# Option_EMCC_Flash.net
KiCad netlist of a schematic drawn in Altium Designer
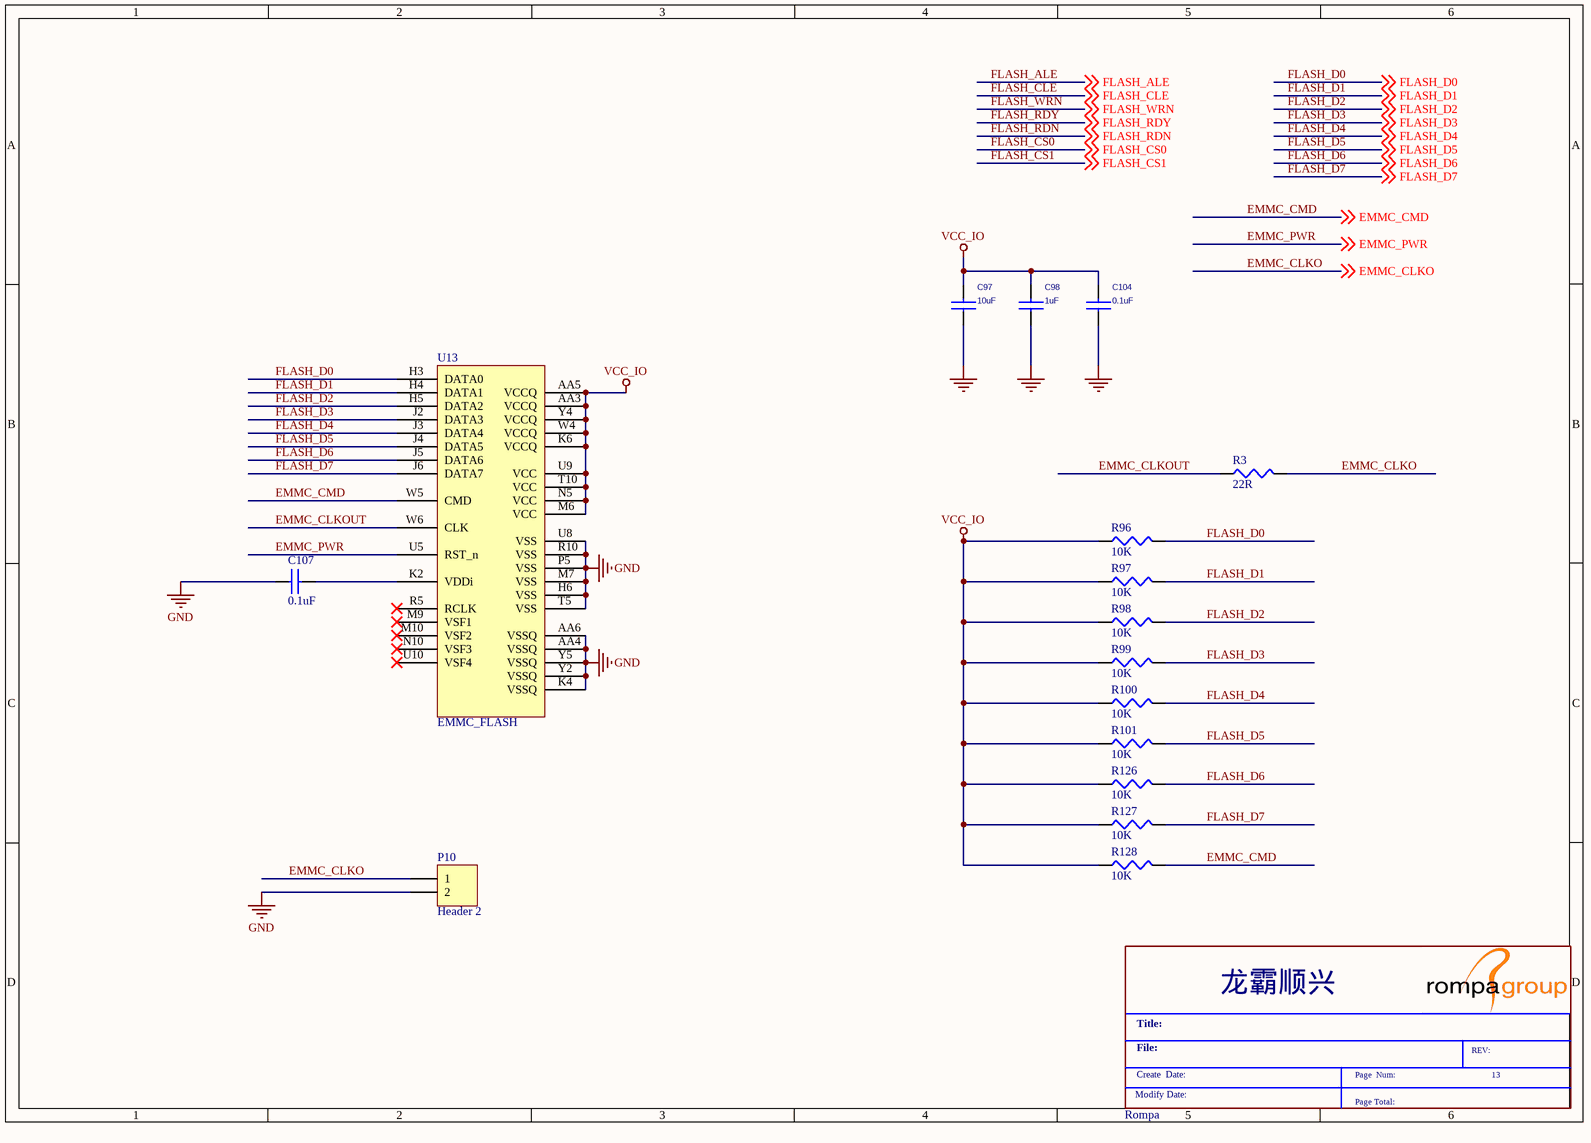
[diagram p0: Option_EMCC_Flash.SchDoc]

(export (version "E")
  (design (tool "Eeschema 10.0.6"))
  (components
    (comp (ref "*")
      (value "Rompa")
      (fields (field (name "SCHEMATIC PAGE NUMBER") "13"))
      (libsource (lib "RK3128_BETA_V03_20151231_Library") (part "Rompa"))
    )
    (comp (ref "C97") (value "10uF") (description "X5R 10%  6.3V") (libsource (lib "*") (part "CAP NP")))
    (comp (ref "C98") (value "1uF") (description "+10/-10% X5R  6.3V") (libsource (lib "*") (part "CAP NP")))
    (comp (ref "C104")
      (value "0.1uF")
      (footprint "C0402")
      (description "RoHS CHIP CAP 0.1uF +10/-10% X7R")
      (libsource (lib "*") (part "CAP NP"))
    )
    (comp (ref "C107")
      (value "0.1uF")
      (footprint "C0402")
      (libsource (lib "RK3128_BETA_V03_20151231_Library") (part "CAP NP"))
    )
    (comp (ref "P10")
      (value "Header 2")
      (footprint "HDR1X2")
      (description "Header, 2-Pin")
      (fields (field (name "PUBLISHER") "Altium Limited"))
      (libsource (lib "Miscellaneous Connectors") (part "Header 2"))
    )
    (comp (ref "R3")
      (value "22R")
      (footprint "R0402")
      (libsource (lib "RK3128_BETA_V03_20151231_Library") (part "RESISTOR"))
    )
    (comp (ref "R96")
      (value "10K")
      (footprint "R0402")
      (libsource (lib "RK3128_BETA_V03_20151231_Library") (part "RESISTOR"))
    )
    (comp (ref "R97")
      (value "10K")
      (footprint "R0402")
      (libsource (lib "RK3128_BETA_V03_20151231_Library") (part "RESISTOR"))
    )
    (comp (ref "R98")
      (value "10K")
      (footprint "R0402")
      (libsource (lib "RK3128_BETA_V03_20151231_Library") (part "RESISTOR"))
    )
    (comp (ref "R99")
      (value "10K")
      (footprint "R0402")
      (libsource (lib "RK3128_BETA_V03_20151231_Library") (part "RESISTOR"))
    )
    (comp (ref "R100")
      (value "10K")
      (footprint "R0402")
      (libsource (lib "RK3128_BETA_V03_20151231_Library") (part "RESISTOR"))
    )
    (comp (ref "R101")
      (value "10K")
      (footprint "R0402")
      (libsource (lib "RK3128_BETA_V03_20151231_Library") (part "RESISTOR"))
    )
    (comp (ref "R126")
      (value "10K")
      (footprint "R0402")
      (libsource (lib "RK3128_BETA_V03_20151231_Library") (part "RESISTOR"))
    )
    (comp (ref "R127")
      (value "10K")
      (footprint "R0402")
      (libsource (lib "RK3128_BETA_V03_20151231_Library") (part "RESISTOR"))
    )
    (comp (ref "R128")
      (value "10K")
      (footprint "R0402")
      (libsource (lib "RK3128_BETA_V03_20151231_Library") (part "RESISTOR"))
    )
    (comp (ref "U13")
      (value "EMMC_FLASH")
      (description "EMMC Flash")
      (libsource (lib "*") (part "EMMC_FLASH"))
    )
  )
  (nets
    (net (code "1") (name "/EMMC_CLKOUT") (class "Default")
      (node (ref "R3") (pin "1") (pinfunction "1_1") (pintype "passive"))
      (node (ref "U13") (pin "W6") (pinfunction "CLK_W6") (pintype "passive"))
    )
    (net (code "2") (name "EMMC_CLKO") (class "Default")
      (node (ref "P10") (pin "1") (pinfunction "1_1") (pintype "passive"))
      (node (ref "R3") (pin "2") (pinfunction "2_2") (pintype "passive"))
    )
    (net (code "3") (name "EMMC_CMD") (class "Default")
      (node (ref "R128") (pin "2") (pinfunction "2_2") (pintype "passive"))
      (node (ref "U13") (pin "W5") (pinfunction "CMD_W5") (pintype "passive"))
    )
    (net (code "4") (name "EMMC_PWR") (class "Default")
      (node (ref "U13") (pin "U5") (pinfunction "RST_n_U5") (pintype "passive"))
    )
    (net (code "9") (name "FLASH_D0") (class "Default")
      (node (ref "R96") (pin "2") (pinfunction "2_2") (pintype "passive"))
      (node (ref "U13") (pin "H3") (pinfunction "DATA0_H3") (pintype "passive"))
    )
    (net (code "10") (name "FLASH_D1") (class "Default")
      (node (ref "R97") (pin "2") (pinfunction "2_2") (pintype "passive"))
      (node (ref "U13") (pin "H4") (pinfunction "DATA1_H4") (pintype "passive"))
    )
    (net (code "11") (name "FLASH_D2") (class "Default")
      (node (ref "R98") (pin "2") (pinfunction "2_2") (pintype "passive"))
      (node (ref "U13") (pin "H5") (pinfunction "DATA2_H5") (pintype "passive"))
    )
    (net (code "12") (name "FLASH_D3") (class "Default")
      (node (ref "R99") (pin "2") (pinfunction "2_2") (pintype "passive"))
      (node (ref "U13") (pin "J2") (pinfunction "DATA3_J2") (pintype "passive"))
    )
    (net (code "13") (name "FLASH_D4") (class "Default")
      (node (ref "R100") (pin "2") (pinfunction "2_2") (pintype "passive"))
      (node (ref "U13") (pin "J3") (pinfunction "DATA4_J3") (pintype "passive"))
    )
    (net (code "14") (name "FLASH_D5") (class "Default")
      (node (ref "R101") (pin "2") (pinfunction "2_2") (pintype "passive"))
      (node (ref "U13") (pin "J4") (pinfunction "DATA5_J4") (pintype "passive"))
    )
    (net (code "15") (name "FLASH_D6") (class "Default")
      (node (ref "R126") (pin "2") (pinfunction "2_2") (pintype "passive"))
      (node (ref "U13") (pin "J5") (pinfunction "DATA6_J5") (pintype "passive"))
    )
    (net (code "16") (name "FLASH_D7") (class "Default")
      (node (ref "R127") (pin "2") (pinfunction "2_2") (pintype "passive"))
      (node (ref "U13") (pin "J6") (pinfunction "DATA7_J6") (pintype "passive"))
    )
    (net (code "20") (name "GND") (class "Default")
      (node (ref "C104") (pin "1") (pinfunction "1_1") (pintype "passive"))
      (node (ref "C107") (pin "1") (pinfunction "1_1") (pintype "passive"))
      (node (ref "C97") (pin "1") (pinfunction "1_1") (pintype "passive"))
      (node (ref "C98") (pin "1") (pinfunction "1_1") (pintype "passive"))
      (node (ref "P10") (pin "2") (pinfunction "2_2") (pintype "passive"))
      (node (ref "U13") (pin "AA4") (pinfunction "VSSQ_AA4") (pintype "passive"))
      (node (ref "U13") (pin "AA6") (pinfunction "VSSQ_AA6") (pintype "passive"))
      (node (ref "U13") (pin "H6") (pinfunction "VSS_H6") (pintype "passive"))
      (node (ref "U13") (pin "K4") (pinfunction "VSSQ_K4") (pintype "passive"))
      (node (ref "U13") (pin "M7") (pinfunction "VSS_M7") (pintype "passive"))
      (node (ref "U13") (pin "P5") (pinfunction "VSS_P5") (pintype "passive"))
      (node (ref "U13") (pin "R10") (pinfunction "VSS_R10") (pintype "passive"))
      (node (ref "U13") (pin "T5") (pinfunction "VSS_T5") (pintype "passive"))
      (node (ref "U13") (pin "U8") (pinfunction "VSS_U8") (pintype "passive"))
      (node (ref "U13") (pin "Y2") (pinfunction "VSSQ_Y2") (pintype "passive"))
      (node (ref "U13") (pin "Y5") (pinfunction "VSSQ_Y5") (pintype "passive"))
    )
    (net (code "21") (name "Net-(U13-VDDi)") (class "Default")
      (node (ref "C107") (pin "2") (pinfunction "2_2") (pintype "passive"))
      (node (ref "U13") (pin "K2") (pinfunction "VDDi_K2") (pintype "passive"))
    )
    (net (code "22") (name "VCC_IO") (class "Default")
      (node (ref "C104") (pin "2") (pinfunction "2_2") (pintype "passive"))
      (node (ref "C97") (pin "2") (pinfunction "2_2") (pintype "passive"))
      (node (ref "C98") (pin "2") (pinfunction "2_2") (pintype "passive"))
      (node (ref "R100") (pin "1") (pinfunction "1_1") (pintype "passive"))
      (node (ref "R101") (pin "1") (pinfunction "1_1") (pintype "passive"))
      (node (ref "R126") (pin "1") (pinfunction "1_1") (pintype "passive"))
      (node (ref "R127") (pin "1") (pinfunction "1_1") (pintype "passive"))
      (node (ref "R128") (pin "1") (pinfunction "1_1") (pintype "passive"))
      (node (ref "R96") (pin "1") (pinfunction "1_1") (pintype "passive"))
      (node (ref "R97") (pin "1") (pinfunction "1_1") (pintype "passive"))
      (node (ref "R98") (pin "1") (pinfunction "1_1") (pintype "passive"))
      (node (ref "R99") (pin "1") (pinfunction "1_1") (pintype "passive"))
      (node (ref "U13") (pin "AA3") (pinfunction "VCCQ_AA3") (pintype "passive"))
      (node (ref "U13") (pin "AA5") (pinfunction "VCCQ_AA5") (pintype "passive"))
      (node (ref "U13") (pin "K6") (pinfunction "VCCQ_K6") (pintype "passive"))
      (node (ref "U13") (pin "M6") (pinfunction "VCC_M6") (pintype "passive"))
      (node (ref "U13") (pin "N5") (pinfunction "VCC_N5") (pintype "passive"))
      (node (ref "U13") (pin "T10") (pinfunction "VCC_T10") (pintype "passive"))
      (node (ref "U13") (pin "U9") (pinfunction "VCC_U9") (pintype "passive"))
      (node (ref "U13") (pin "W4") (pinfunction "VCCQ_W4") (pintype "passive"))
      (node (ref "U13") (pin "Y4") (pinfunction "VCCQ_Y4") (pintype "passive"))
    )
    (net (code "23") (name "unconnected-(U13-RCLK-PadR5)") (class "Default")
      (node (ref "U13") (pin "R5") (pinfunction "RCLK_R5") (pintype "passive+no_connect"))
    )
    (net (code "24") (name "unconnected-(U13-VSF1-PadM9)") (class "Default")
      (node (ref "U13") (pin "M9") (pinfunction "VSF1_M9") (pintype "passive+no_connect"))
    )
    (net (code "25") (name "unconnected-(U13-VSF2-PadM10)") (class "Default")
      (node (ref "U13") (pin "M10") (pinfunction "VSF2_M10") (pintype "passive+no_connect"))
    )
    (net (code "26") (name "unconnected-(U13-VSF3-PadN10)") (class "Default")
      (node (ref "U13") (pin "N10") (pinfunction "VSF3_N10") (pintype "passive+no_connect"))
    )
    (net (code "27") (name "unconnected-(U13-VSF4-PadU10)") (class "Default")
      (node (ref "U13") (pin "U10") (pinfunction "VSF4_U10") (pintype "passive+no_connect"))
    )
  )
)
